# STM32_EVK_2.net
KiCad netlist of a schematic drawn in Altium Designer
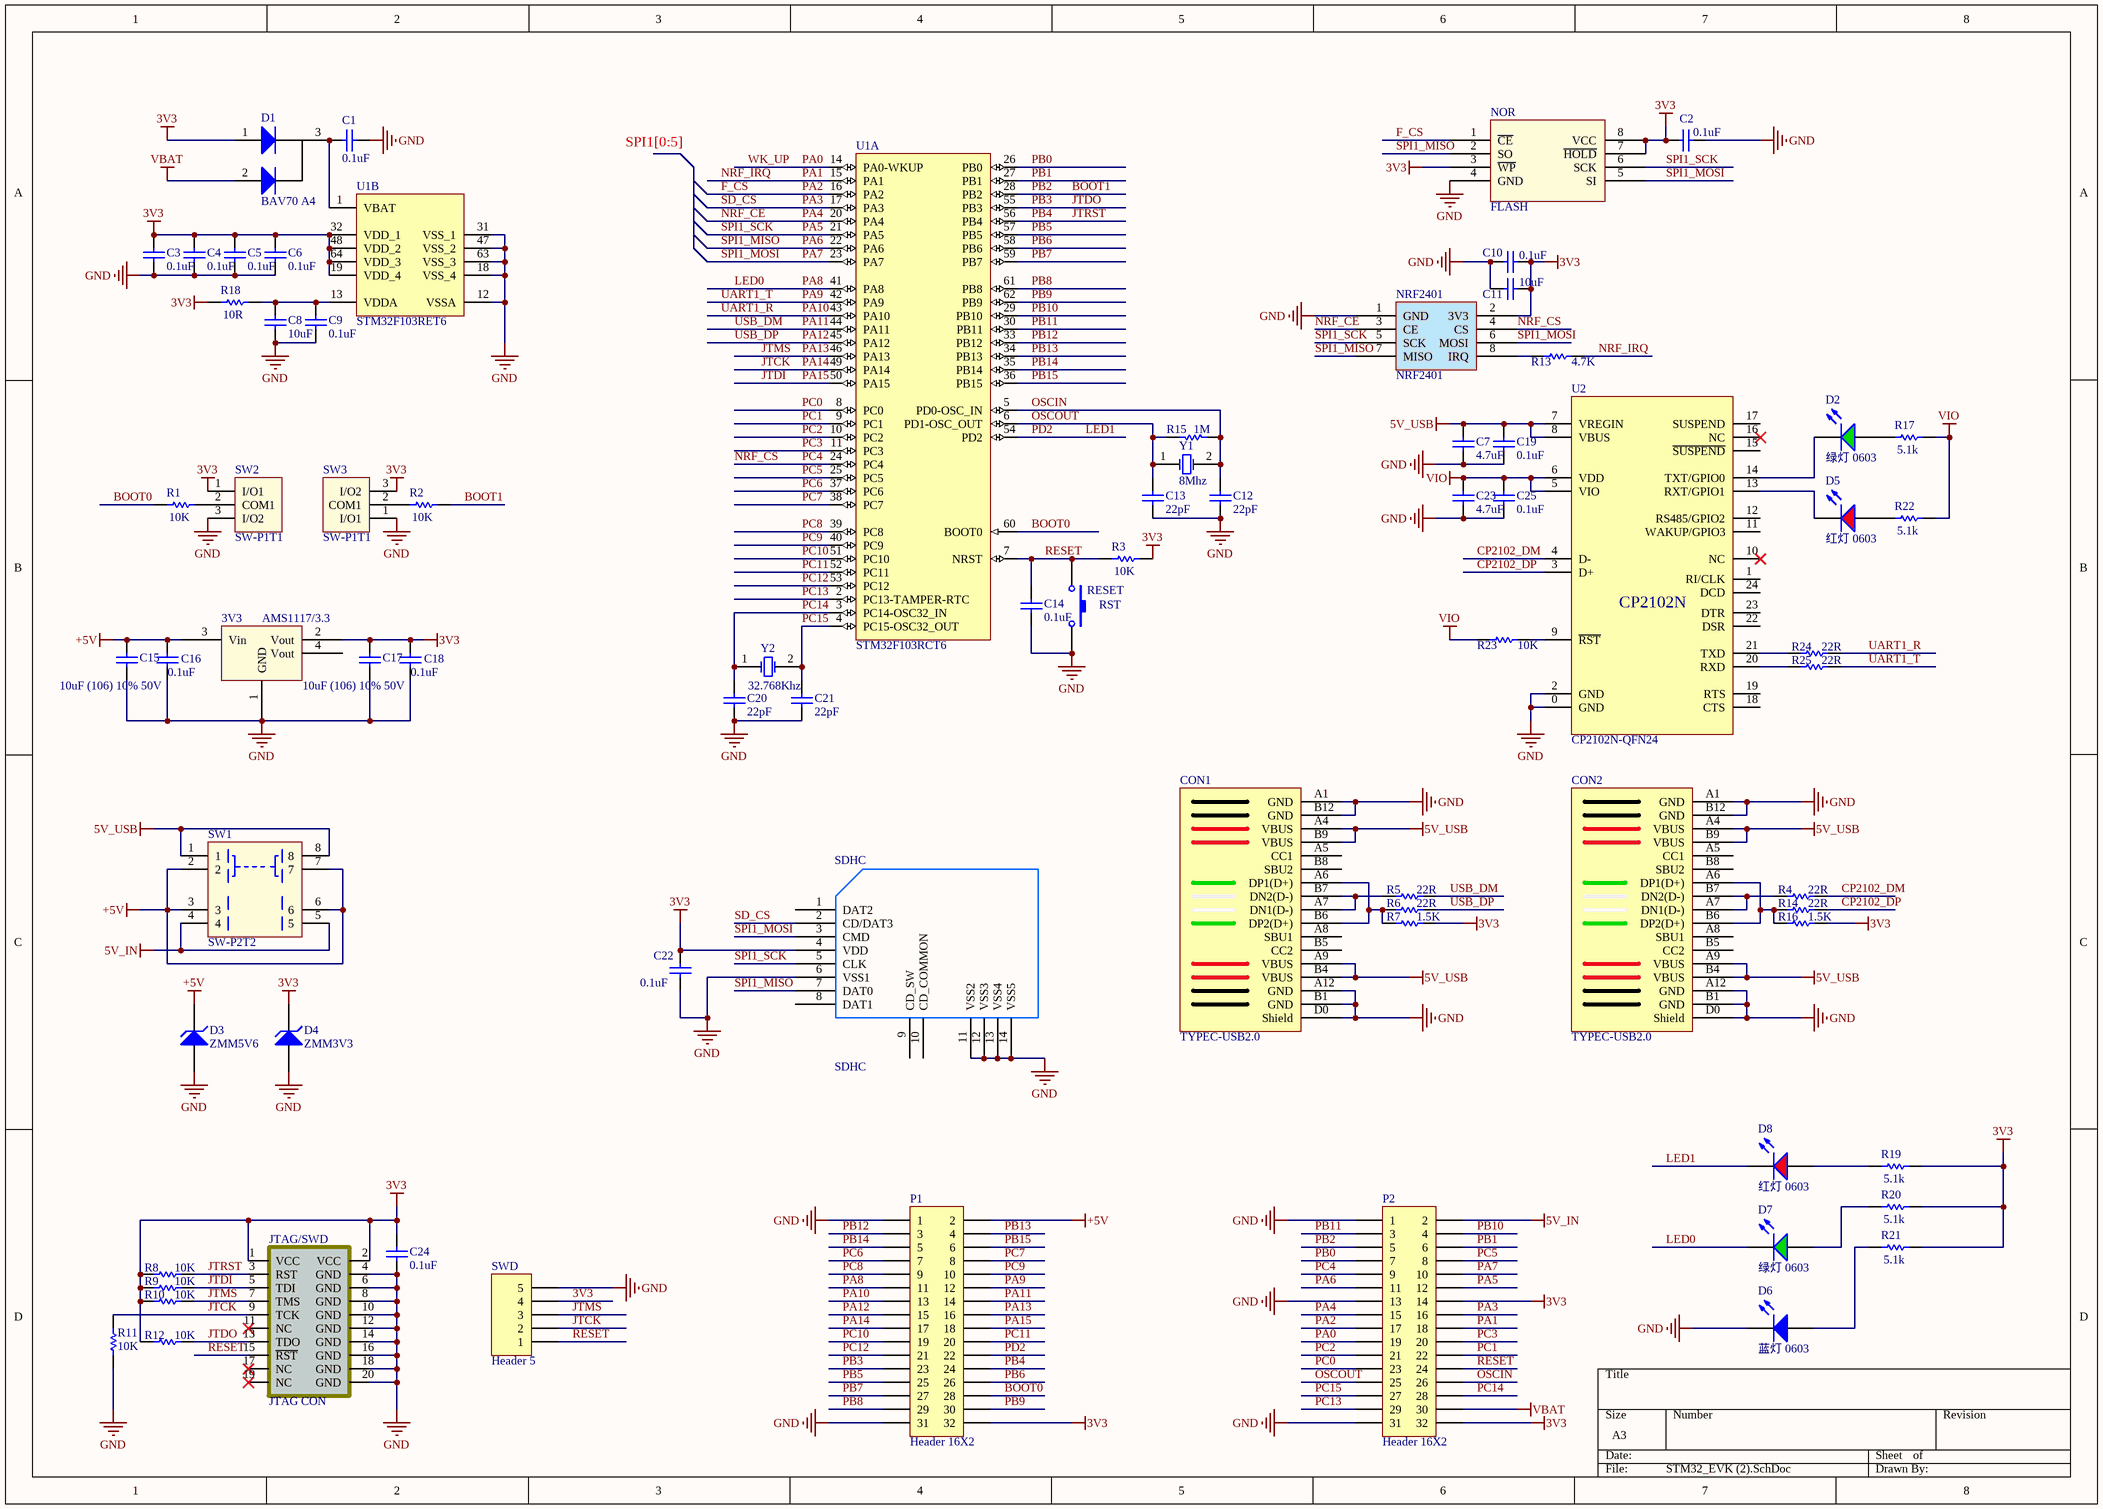
[diagram p0: STM32_EVK (2).SchDoc]

(export (version "E")
  (design (tool "Eeschema 10.0.6"))
  (components
    (comp (ref "3V3") (value "AMS1117/3.3") (footprint "LC-SOT-223") (libsource (lib "YJ1") (part "AMS1117")))
    (comp (ref "C1")
      (value "0.1uF")
      (footprint "LC-0603_C")
      (description "Capacitor")
      (fields (field (name "Comment") "Cap") (field (name "PUBLISHER") "Altium Limited"))
      (libsource (lib "Miscellaneous Devices") (part "Cap"))
    )
    (comp (ref "C2")
      (value "0.1uF")
      (footprint "LC-0603_C")
      (description "Capacitor")
      (fields (field (name "Comment") "Cap") (field (name "PUBLISHER") "Altium Limited"))
      (libsource (lib "Miscellaneous Devices") (part "Cap"))
    )
    (comp (ref "C3")
      (value "0.1uF")
      (footprint "LC-0603_C")
      (description "Capacitor")
      (fields (field (name "Comment") "Cap") (field (name "PUBLISHER") "Altium Limited"))
      (libsource (lib "Miscellaneous Devices") (part "Cap"))
    )
    (comp (ref "C4")
      (value "0.1uF")
      (footprint "LC-0603_C")
      (description "Capacitor")
      (fields (field (name "Comment") "Cap") (field (name "PUBLISHER") "Altium Limited"))
      (libsource (lib "Miscellaneous Devices") (part "Cap"))
    )
    (comp (ref "C5")
      (value "0.1uF")
      (footprint "LC-0603_C")
      (description "Capacitor")
      (fields (field (name "Comment") "Cap") (field (name "PUBLISHER") "Altium Limited"))
      (libsource (lib "Miscellaneous Devices") (part "Cap"))
    )
    (comp (ref "C6")
      (value "0.1uF")
      (footprint "LC-0603_C")
      (description "Capacitor")
      (fields (field (name "Comment") "Cap") (field (name "PUBLISHER") "Altium Limited"))
      (libsource (lib "Miscellaneous Devices") (part "Cap"))
    )
    (comp (ref "C7")
      (value "4.7uF")
      (footprint "LC-0603_C")
      (description "Capacitor")
      (fields (field (name "Comment") "Cap") (field (name "PUBLISHER") "Altium Limited"))
      (libsource (lib "Miscellaneous Devices") (part "Cap"))
    )
    (comp (ref "C8")
      (value "10uF")
      (footprint "LC-0603_C")
      (description "Capacitor")
      (fields (field (name "Comment") "Cap") (field (name "PUBLISHER") "Altium Limited"))
      (libsource (lib "Miscellaneous Devices") (part "Cap"))
    )
    (comp (ref "C9")
      (value "0.1uF")
      (footprint "LC-0603_C")
      (description "Capacitor")
      (fields (field (name "Comment") "Cap") (field (name "PUBLISHER") "Altium Limited"))
      (libsource (lib "Miscellaneous Devices") (part "Cap"))
    )
    (comp (ref "C10")
      (value "0.1uF")
      (footprint "LC-0603_C")
      (description "Capacitor")
      (fields (field (name "Comment") "Cap") (field (name "PUBLISHER") "Altium Limited"))
      (libsource (lib "Miscellaneous Devices") (part "Cap"))
    )
    (comp (ref "C11")
      (value "10uF")
      (footprint "LC-0603_C")
      (description "Capacitor")
      (fields (field (name "Comment") "Cap") (field (name "PUBLISHER") "Altium Limited"))
      (libsource (lib "Miscellaneous Devices") (part "Cap"))
    )
    (comp (ref "C12")
      (value "22pF")
      (footprint "LC-0603_C")
      (description "Capacitor")
      (fields (field (name "Comment") "Cap") (field (name "PUBLISHER") "Altium Limited"))
      (libsource (lib "Miscellaneous Devices") (part "Cap"))
    )
    (comp (ref "C13")
      (value "22pF")
      (footprint "LC-0603_C")
      (description "Capacitor")
      (fields (field (name "Comment") "Cap") (field (name "PUBLISHER") "Altium Limited"))
      (libsource (lib "Miscellaneous Devices") (part "Cap"))
    )
    (comp (ref "C14")
      (value "0.1uF")
      (footprint "LC-0603_C")
      (description "Capacitor")
      (fields (field (name "Comment") "Cap") (field (name "PUBLISHER") "Altium Limited"))
      (libsource (lib "Miscellaneous Devices") (part "Cap"))
    )
    (comp (ref "C15")
      (value "10uF (106) 10% 50V")
      (footprint "LC-1206_C")
      (description "贴片电容")
      (libsource (lib "Miscellaneous Devices LC") (part "1206 10uF (106) 10% 50V"))
    )
    (comp (ref "C16")
      (value "0.1uF")
      (footprint "LC-0603_C")
      (description "Capacitor (Semiconductor SIM Model)")
      (fields (field (name "Comment") "Cap Semi") (field (name "PUBLISHER") "Altium Limited"))
      (libsource (lib "Miscellaneous Devices") (part "Cap Semi"))
    )
    (comp (ref "C17")
      (value "10uF (106) 10% 50V")
      (footprint "LC-1206_C")
      (description "贴片电容")
      (libsource (lib "Miscellaneous Devices LC") (part "1206 10uF (106) 10% 50V"))
    )
    (comp (ref "C18")
      (value "0.1uF")
      (footprint "LC-0603_C")
      (description "Capacitor (Semiconductor SIM Model)")
      (fields (field (name "Comment") "Cap Semi") (field (name "PUBLISHER") "Altium Limited"))
      (libsource (lib "Miscellaneous Devices") (part "Cap Semi"))
    )
    (comp (ref "C19")
      (value "0.1uF")
      (footprint "LC-0603_C")
      (description "Capacitor")
      (fields (field (name "Comment") "Cap") (field (name "PUBLISHER") "Altium Limited"))
      (libsource (lib "Miscellaneous Devices") (part "Cap"))
    )
    (comp (ref "C20")
      (value "22pF")
      (footprint "LC-0603_C")
      (description "Capacitor")
      (fields (field (name "Comment") "Cap") (field (name "PUBLISHER") "Altium Limited"))
      (libsource (lib "Miscellaneous Devices") (part "Cap"))
    )
    (comp (ref "C21")
      (value "22pF")
      (footprint "LC-0603_C")
      (description "Capacitor")
      (fields (field (name "Comment") "Cap") (field (name "PUBLISHER") "Altium Limited"))
      (libsource (lib "Miscellaneous Devices") (part "Cap"))
    )
    (comp (ref "C22")
      (value "0.1uF")
      (footprint "LC-0603_C")
      (description "Capacitor")
      (fields (field (name "Comment") "Cap") (field (name "PUBLISHER") "Altium Limited"))
      (libsource (lib "Miscellaneous Devices") (part "Cap"))
    )
    (comp (ref "C23")
      (value "4.7uF")
      (footprint "LC-0603_C")
      (description "Capacitor")
      (fields (field (name "Comment") "Cap") (field (name "PUBLISHER") "Altium Limited"))
      (libsource (lib "Miscellaneous Devices") (part "Cap"))
    )
    (comp (ref "C24")
      (value "0.1uF")
      (footprint "LC-0603_C")
      (description "Capacitor")
      (fields (field (name "Comment") "Cap") (field (name "PUBLISHER") "Altium Limited"))
      (libsource (lib "Miscellaneous Devices") (part "Cap"))
    )
    (comp (ref "C25")
      (value "0.1uF")
      (footprint "LC-0603_C")
      (description "Capacitor")
      (fields (field (name "Comment") "Cap") (field (name "PUBLISHER") "Altium Limited"))
      (libsource (lib "Miscellaneous Devices") (part "Cap"))
    )
    (comp (ref "CON1")
      (value "TYPEC-USB2.0")
      (footprint "TYPEC-USB2.0")
      (libsource (lib "YJ1") (part "TYPEC-USB2.0"))
    )
    (comp (ref "CON2")
      (value "TYPEC-USB2.0")
      (footprint "TYPEC-USB2.0")
      (libsource (lib "YJ1") (part "TYPEC-USB2.0"))
    )
    (comp (ref "D1")
      (value "BAV70 A4")
      (footprint "LC-SOT-23(SOT-23-3)")
      (description "开关二极管")
      (libsource (lib "Miscellaneous Devices LC") (part "SOT-23 BAV70 A4"))
    )
    (comp (ref "D2")
      (value "绿灯 0603")
      (footprint "LC-0603_LED_S1")
      (description "发光二极管")
      (libsource (lib "Miscellaneous Devices LC") (part "0603 绿灯"))
    )
    (comp (ref "D3")
      (value "ZMM5V6")
      (footprint "LC-LL-34")
      (description "稳压二极管")
      (libsource (lib "Miscellaneous Devices LC") (part "LL-34 ZMM5V6"))
    )
    (comp (ref "D4")
      (value "ZMM3V3")
      (footprint "LC-LL-34")
      (description "稳压二极管")
      (libsource (lib "Miscellaneous Devices LC") (part "LL-34 ZMM3V3"))
    )
    (comp (ref "D5")
      (value "红灯 0603")
      (footprint "LC-0603_LED_S1")
      (description "发光二极管")
      (libsource (lib "Miscellaneous Devices LC") (part "0603 红灯"))
    )
    (comp (ref "D6")
      (value "蓝灯 0603")
      (footprint "LC-0603_LED_S1")
      (description "发光二极管")
      (libsource (lib "Miscellaneous Devices LC") (part "0603 蓝灯"))
    )
    (comp (ref "D7")
      (value "绿灯 0603")
      (footprint "LC-0603_LED_S1")
      (description "发光二极管")
      (libsource (lib "Miscellaneous Devices LC") (part "0603 绿灯"))
    )
    (comp (ref "D8")
      (value "红灯 0603")
      (footprint "LC-0603_LED_S1")
      (description "发光二极管")
      (libsource (lib "Miscellaneous Devices LC") (part "0603 红灯"))
    )
    (comp (ref "JTAG/SWD") (value "JTAG CON") (footprint "20Pin简牛") (libsource (lib "STM32F4") (part "JTAG")))
    (comp (ref "NOR") (value "FLASH") (footprint "M25P32_SOP8W") (libsource (lib "YJ1") (part "FLASH")))
    (comp (ref "NRF2401") (value "NRF2401") (footprint "HDR2X4") (libsource (lib "YJ1") (part "NRF2401")))
    (comp (ref "P1")
      (value "Header 16X2")
      (footprint "HDR2X16")
      (description "Header, 16-Pin, Dual row")
      (fields (field (name "PUBLISHER") "Altium Limited"))
      (libsource (lib "Miscellaneous Connectors") (part "Header 16X2"))
    )
    (comp (ref "P2")
      (value "Header 16X2")
      (footprint "HDR2X16")
      (description "Header, 16-Pin, Dual row")
      (fields (field (name "PUBLISHER") "Altium Limited"))
      (libsource (lib "Miscellaneous Connectors") (part "Header 16X2"))
    )
    (comp (ref "R1")
      (value "10K")
      (footprint "LC-0603_R")
      (description "Semiconductor Resistor")
      (fields (field (name "Comment") "Res Semi") (field (name "PUBLISHER") "Altium Limited"))
      (libsource (lib "Miscellaneous Devices") (part "Res Semi"))
    )
    (comp (ref "R2")
      (value "10K")
      (footprint "LC-0603_R")
      (description "Semiconductor Resistor")
      (fields (field (name "Comment") "Res Semi") (field (name "PUBLISHER") "Altium Limited"))
      (libsource (lib "Miscellaneous Devices") (part "Res Semi"))
    )
    (comp (ref "R3")
      (value "10K")
      (footprint "LC-0603_R")
      (description "Semiconductor Resistor")
      (fields (field (name "Comment") "Res Semi") (field (name "PUBLISHER") "Altium Limited"))
      (libsource (lib "Miscellaneous Devices") (part "Res Semi"))
    )
    (comp (ref "R4")
      (value "22R")
      (footprint "LC-0603_R")
      (description "Semiconductor Resistor")
      (fields (field (name "Comment") "Res Semi") (field (name "PUBLISHER") "Altium Limited"))
      (libsource (lib "Miscellaneous Devices") (part "Res Semi"))
    )
    (comp (ref "R5")
      (value "22R")
      (footprint "LC-0603_R")
      (description "Semiconductor Resistor")
      (fields (field (name "Comment") "Res Semi") (field (name "PUBLISHER") "Altium Limited"))
      (libsource (lib "Miscellaneous Devices") (part "Res Semi"))
    )
    (comp (ref "R6")
      (value "22R")
      (footprint "LC-0603_R")
      (description "Semiconductor Resistor")
      (fields (field (name "Comment") "Res Semi") (field (name "PUBLISHER") "Altium Limited"))
      (libsource (lib "Miscellaneous Devices") (part "Res Semi"))
    )
    (comp (ref "R7")
      (value "1.5K")
      (footprint "LC-0603_R")
      (description "Semiconductor Resistor")
      (fields (field (name "Comment") "Res Semi") (field (name "PUBLISHER") "Altium Limited"))
      (libsource (lib "Miscellaneous Devices") (part "Res Semi"))
    )
    (comp (ref "R8")
      (value "10K")
      (footprint "LC-0603_R")
      (description "Semiconductor Resistor")
      (fields (field (name "Comment") "Res Semi") (field (name "PUBLISHER") "Altium Limited"))
      (libsource (lib "Miscellaneous Devices") (part "Res Semi"))
    )
    (comp (ref "R9")
      (value "10K")
      (footprint "LC-0603_R")
      (description "Semiconductor Resistor")
      (fields (field (name "Comment") "Res Semi") (field (name "PUBLISHER") "Altium Limited"))
      (libsource (lib "Miscellaneous Devices") (part "Res Semi"))
    )
    (comp (ref "R10")
      (value "10K")
      (footprint "LC-0603_R")
      (description "Semiconductor Resistor")
      (fields (field (name "Comment") "Res Semi") (field (name "PUBLISHER") "Altium Limited"))
      (libsource (lib "Miscellaneous Devices") (part "Res Semi"))
    )
    (comp (ref "R11")
      (value "10K")
      (footprint "LC-0603_R")
      (description "Semiconductor Resistor")
      (fields (field (name "Comment") "Res Semi") (field (name "PUBLISHER") "Altium Limited"))
      (libsource (lib "Miscellaneous Devices") (part "Res Semi"))
    )
    (comp (ref "R12")
      (value "10K")
      (footprint "LC-0603_R")
      (description "Semiconductor Resistor")
      (fields (field (name "Comment") "Res Semi") (field (name "PUBLISHER") "Altium Limited"))
      (libsource (lib "Miscellaneous Devices") (part "Res Semi"))
    )
    (comp (ref "R13")
      (value "4.7K")
      (footprint "LC-0603_R")
      (description "Semiconductor Resistor")
      (fields (field (name "Comment") "Res Semi") (field (name "PUBLISHER") "Altium Limited"))
      (libsource (lib "Miscellaneous Devices") (part "Res Semi"))
    )
    (comp (ref "R14")
      (value "22R")
      (footprint "LC-0603_R")
      (description "Semiconductor Resistor")
      (fields (field (name "Comment") "Res Semi") (field (name "PUBLISHER") "Altium Limited"))
      (libsource (lib "Miscellaneous Devices") (part "Res Semi"))
    )
    (comp (ref "R15")
      (value "1M")
      (footprint "LC-0603_R")
      (description "Semiconductor Resistor")
      (fields (field (name "Comment") "Res Semi") (field (name "PUBLISHER") "Altium Limited"))
      (libsource (lib "Miscellaneous Devices") (part "Res Semi"))
    )
    (comp (ref "R16")
      (value "1.5K")
      (footprint "LC-0603_R")
      (description "Semiconductor Resistor")
      (fields (field (name "Comment") "Res Semi") (field (name "PUBLISHER") "Altium Limited"))
      (libsource (lib "Miscellaneous Devices") (part "Res Semi"))
    )
    (comp (ref "R17")
      (value "5.1k")
      (footprint "LC-0603_R")
      (description "Semiconductor Resistor")
      (fields (field (name "Comment") "Res Semi") (field (name "PUBLISHER") "Altium Limited"))
      (libsource (lib "Miscellaneous Devices") (part "Res Semi"))
    )
    (comp (ref "R18")
      (value "10R")
      (footprint "LC-0603_R")
      (description "Semiconductor Resistor")
      (fields (field (name "Comment") "Res Semi") (field (name "PUBLISHER") "Altium Limited"))
      (libsource (lib "Miscellaneous Devices") (part "Res Semi"))
    )
    (comp (ref "R19")
      (value "5.1k")
      (footprint "LC-0603_R")
      (description "Semiconductor Resistor")
      (fields (field (name "Comment") "Res Semi") (field (name "PUBLISHER") "Altium Limited"))
      (libsource (lib "Miscellaneous Devices") (part "Res Semi"))
    )
    (comp (ref "R20")
      (value "5.1k")
      (footprint "LC-0603_R")
      (description "Semiconductor Resistor")
      (fields (field (name "Comment") "Res Semi") (field (name "PUBLISHER") "Altium Limited"))
      (libsource (lib "Miscellaneous Devices") (part "Res Semi"))
    )
    (comp (ref "R21")
      (value "5.1k")
      (footprint "LC-0603_R")
      (description "Semiconductor Resistor")
      (fields (field (name "Comment") "Res Semi") (field (name "PUBLISHER") "Altium Limited"))
      (libsource (lib "Miscellaneous Devices") (part "Res Semi"))
    )
    (comp (ref "R22")
      (value "5.1k")
      (footprint "LC-0603_R")
      (description "Semiconductor Resistor")
      (fields (field (name "Comment") "Res Semi") (field (name "PUBLISHER") "Altium Limited"))
      (libsource (lib "Miscellaneous Devices") (part "Res Semi"))
    )
    (comp (ref "R23")
      (value "10K")
      (footprint "LC-0603_R")
      (description "Semiconductor Resistor")
      (fields (field (name "Comment") "Res Semi") (field (name "PUBLISHER") "Altium Limited"))
      (libsource (lib "Miscellaneous Devices") (part "Res Semi"))
    )
    (comp (ref "R24")
      (value "22R")
      (footprint "LC-0603_R")
      (description "Semiconductor Resistor")
      (fields (field (name "Comment") "Res Semi") (field (name "PUBLISHER") "Altium Limited"))
      (libsource (lib "Miscellaneous Devices") (part "Res Semi"))
    )
    (comp (ref "R25")
      (value "22R")
      (footprint "LC-0603_R")
      (description "Semiconductor Resistor")
      (fields (field (name "Comment") "Res Semi") (field (name "PUBLISHER") "Altium Limited"))
      (libsource (lib "Miscellaneous Devices") (part "Res Semi"))
    )
    (comp (ref "RESET")
      (value "RST")
      (footprint "ALPS_SKPMA_KEY")
      (description "Switch")
      (fields (field (name "PUBLISHER") "Altium Limited"))
      (libsource (lib "Miscellaneous Devices") (part "SW-PB"))
    )
    (comp (ref "SDHC") (value "SDHC") (footprint "microSD") (libsource (lib "YJ1") (part "SDHC")))
    (comp (ref "SW1") (value "SW-P2T2") (footprint "SW-P2T2") (libsource (lib "YJ1") (part "SW-P2T2")))
    (comp (ref "SW2") (value "SW-P1T1") (footprint "SW-P1T1") (libsource (lib "YJ1") (part "SW-P1T1")))
    (comp (ref "SW3") (value "SW-P1T1") (footprint "SW-P1T1-JUMP") (libsource (lib "") (part "SW-P1T1_1")))
    (comp (ref "SWD")
      (value "Header 5")
      (footprint "HDR1X5")
      (description "Header, 5-Pin")
      (fields (field (name "PUBLISHER") "Altium Limited"))
      (libsource (lib "Miscellaneous Connectors") (part "Header 5"))
    )
    (comp (ref "U1")
      (value "STM32F103RCT6")
      (footprint "LC-LQFP-64_10x10x05P")
      (fields (field (name "PARTNUMBER") "STM32F103RET6"))
      (libsource (lib "STMicroelectronics STM32 F1") (part "STM32F103RET6"))
    )
    (comp (ref "U2")
      (value "CP2102N-QFN24")
      (footprint "LC-QFN-24_4x4x05P")
      (libsource (lib "YJ1") (part "CP2102N-QFN24"))
    )
    (comp (ref "Y1")
      (value "8Mhz")
      (footprint "XTAL-RAD-0.2")
      (description "Crystal Oscillator")
      (fields (field (name "PUBLISHER") "Altium Limited"))
      (libsource (lib "Miscellaneous Devices") (part "XTAL"))
    )
    (comp (ref "Y2")
      (value "32.768Khz")
      (footprint "32768_3*8_圆筒晶振")
      (description "Crystal Oscillator")
      (fields (field (name "PUBLISHER") "Altium Limited"))
      (libsource (lib "Miscellaneous Devices") (part "XTAL"))
    )
  )
  (nets
    (net (code "1") (name "+5V") (class "Default")
      (node (ref "3V3") (pin "3") (pinfunction "Vin_3") (pintype "passive"))
      (node (ref "C15") (pin "2") (pinfunction "2_2") (pintype "passive"))
      (node (ref "C16") (pin "2") (pinfunction "2_2") (pintype "passive"))
      (node (ref "D3") (pin "2") (pinfunction "K_2") (pintype "passive"))
      (node (ref "P1") (pin "2") (pinfunction "2_2") (pintype "passive"))
      (node (ref "SW1") (pin "2") (pinfunction "2_2") (pintype "passive"))
      (node (ref "SW1") (pin "3") (pinfunction "3_3") (pintype "passive"))
      (node (ref "SW1") (pin "6") (pinfunction "6_6") (pintype "passive"))
      (node (ref "SW1") (pin "7") (pinfunction "7_7") (pintype "passive"))
    )
    (net (code "2") (name "/BOOT0") (class "Default")
      (node (ref "P1") (pin "28") (pinfunction "28_28") (pintype "passive"))
      (node (ref "R1") (pin "1") (pinfunction "1_1") (pintype "passive"))
      (node (ref "U1") (pin "60") (pinfunction "BOOT0_60") (pintype "input"))
    )
    (net (code "3") (name "/BOOT1") (class "Default")
      (node (ref "P2") (pin "5") (pinfunction "5_5") (pintype "passive"))
      (node (ref "R2") (pin "2") (pinfunction "2_2") (pintype "passive"))
      (node (ref "U1") (pin "28") (pinfunction "PB2_28") (pintype "bidirectional"))
    )
    (net (code "4") (name "/CP2102_DM") (class "Default")
      (node (ref "R4") (pin "2") (pinfunction "2_2") (pintype "passive"))
      (node (ref "U2") (pin "4") (pinfunction "D-_4") (pintype "passive"))
    )
    (net (code "5") (name "/CP2102_DP") (class "Default")
      (node (ref "R14") (pin "2") (pinfunction "2_2") (pintype "passive"))
      (node (ref "U2") (pin "3") (pinfunction "D+_3") (pintype "passive"))
    )
    (net (code "6") (name "/F_CS") (class "Default")
      (node (ref "NOR") (pin "1") (pinfunction "~{CE}_1") (pintype "passive"))
      (node (ref "P2") (pin "17") (pinfunction "17_17") (pintype "passive"))
      (node (ref "U1") (pin "16") (pinfunction "PA2_16") (pintype "bidirectional"))
    )
    (net (code "7") (name "/JTCK") (class "Default")
      (node (ref "JTAG/SWD") (pin "9") (pinfunction "TCK_9") (pintype "passive"))
      (node (ref "P1") (pin "17") (pinfunction "17_17") (pintype "passive"))
      (node (ref "R11") (pin "2") (pinfunction "2_2") (pintype "passive"))
      (node (ref "SWD") (pin "2") (pinfunction "2_2") (pintype "passive"))
      (node (ref "U1") (pin "49") (pinfunction "PA14_49") (pintype "bidirectional"))
    )
    (net (code "8") (name "/JTDI") (class "Default")
      (node (ref "JTAG/SWD") (pin "5") (pinfunction "TDI_5") (pintype "passive"))
      (node (ref "P1") (pin "18") (pinfunction "18_18") (pintype "passive"))
      (node (ref "R9") (pin "2") (pinfunction "2_2") (pintype "passive"))
      (node (ref "U1") (pin "50") (pinfunction "PA15_50") (pintype "bidirectional"))
    )
    (net (code "9") (name "/JTDO") (class "Default")
      (node (ref "JTAG/SWD") (pin "13") (pinfunction "TDO_13") (pintype "passive"))
      (node (ref "P1") (pin "23") (pinfunction "23_23") (pintype "passive"))
      (node (ref "R12") (pin "2") (pinfunction "2_2") (pintype "passive"))
      (node (ref "U1") (pin "55") (pinfunction "PB3_55") (pintype "bidirectional"))
    )
    (net (code "10") (name "/JTMS") (class "Default")
      (node (ref "JTAG/SWD") (pin "7") (pinfunction "TMS_7") (pintype "passive"))
      (node (ref "P1") (pin "16") (pinfunction "16_16") (pintype "passive"))
      (node (ref "R10") (pin "2") (pinfunction "2_2") (pintype "passive"))
      (node (ref "SWD") (pin "3") (pinfunction "3_3") (pintype "passive"))
      (node (ref "U1") (pin "46") (pinfunction "PA13_46") (pintype "bidirectional"))
    )
    (net (code "11") (name "/JTRST") (class "Default")
      (node (ref "JTAG/SWD") (pin "3") (pinfunction "RST_3") (pintype "passive"))
      (node (ref "P1") (pin "24") (pinfunction "24_24") (pintype "passive"))
      (node (ref "R8") (pin "2") (pinfunction "2_2") (pintype "passive"))
      (node (ref "U1") (pin "56") (pinfunction "PB4_56") (pintype "bidirectional"))
    )
    (net (code "12") (name "/LED0") (class "Default")
      (node (ref "D7") (pin "K") (pinfunction "K_K") (pintype "passive"))
      (node (ref "P1") (pin "11") (pinfunction "11_11") (pintype "passive"))
      (node (ref "U1") (pin "41") (pinfunction "PA8_41") (pintype "bidirectional"))
    )
    (net (code "13") (name "/LED1") (class "Default")
      (node (ref "D8") (pin "K") (pinfunction "K_K") (pintype "passive"))
      (node (ref "P1") (pin "22") (pinfunction "22_22") (pintype "passive"))
      (node (ref "U1") (pin "54") (pinfunction "PD2_54") (pintype "bidirectional"))
    )
    (net (code "14") (name "/NRF_CE") (class "Default")
      (node (ref "NRF2401") (pin "3") (pinfunction "CE_3") (pintype "passive"))
      (node (ref "P2") (pin "15") (pinfunction "15_15") (pintype "passive"))
      (node (ref "U1") (pin "20") (pinfunction "PA4_20") (pintype "bidirectional"))
    )
    (net (code "15") (name "/NRF_CS") (class "Default")
      (node (ref "NRF2401") (pin "4") (pinfunction "CS_4") (pintype "passive"))
      (node (ref "P2") (pin "9") (pinfunction "9_9") (pintype "passive"))
      (node (ref "U1") (pin "24") (pinfunction "PC4_24") (pintype "bidirectional"))
    )
    (net (code "16") (name "/NRF_IRQ") (class "Default")
      (node (ref "P2") (pin "18") (pinfunction "18_18") (pintype "passive"))
      (node (ref "R13") (pin "2") (pinfunction "2_2") (pintype "passive"))
      (node (ref "U1") (pin "15") (pinfunction "PA1_15") (pintype "bidirectional"))
    )
    (net (code "17") (name "/OSCIN") (class "Default")
      (node (ref "C12") (pin "2") (pinfunction "2_2") (pintype "passive"))
      (node (ref "P2") (pin "26") (pinfunction "26_26") (pintype "passive"))
      (node (ref "R15") (pin "1") (pinfunction "1_1") (pintype "passive"))
      (node (ref "U1") (pin "5") (pinfunction "PD0-OSC_IN_5") (pintype "bidirectional"))
      (node (ref "Y1") (pin "2") (pinfunction "OSC2_2") (pintype "passive"))
    )
    (net (code "18") (name "/OSCOUT") (class "Default")
      (node (ref "C13") (pin "2") (pinfunction "2_2") (pintype "passive"))
      (node (ref "P2") (pin "25") (pinfunction "25_25") (pintype "passive"))
      (node (ref "R15") (pin "2") (pinfunction "2_2") (pintype "passive"))
      (node (ref "U1") (pin "6") (pinfunction "PD1-OSC_OUT_6") (pintype "bidirectional"))
      (node (ref "Y1") (pin "1") (pinfunction "OSC1_1") (pintype "passive"))
    )
    (net (code "19") (name "/PA0") (class "Default")
      (node (ref "P2") (pin "19") (pinfunction "19_19") (pintype "passive"))
      (node (ref "U1") (pin "14") (pinfunction "PA0-WKUP_14") (pintype "bidirectional"))
    )
    (net (code "20") (name "/PA3") (class "Default")
      (node (ref "P2") (pin "16") (pinfunction "16_16") (pintype "passive"))
      (node (ref "SDHC") (pin "2") (pinfunction "CD/DAT3_2") (pintype "passive"))
      (node (ref "U1") (pin "17") (pinfunction "PA3_17") (pintype "bidirectional"))
    )
    (net (code "21") (name "/PA5") (class "Default")
      (node (ref "NOR") (pin "6") (pinfunction "SCK_6") (pintype "passive"))
      (node (ref "NRF2401") (pin "5") (pinfunction "SCK_5") (pintype "passive"))
      (node (ref "P2") (pin "12") (pinfunction "12_12") (pintype "passive"))
      (node (ref "SDHC") (pin "5") (pinfunction "CLK_5") (pintype "passive"))
      (node (ref "U1") (pin "21") (pinfunction "PA5_21") (pintype "bidirectional"))
    )
    (net (code "22") (name "/PA6") (class "Default")
      (node (ref "NOR") (pin "2") (pinfunction "SO_2") (pintype "passive"))
      (node (ref "NRF2401") (pin "7") (pinfunction "MISO_7") (pintype "passive"))
      (node (ref "P2") (pin "11") (pinfunction "11_11") (pintype "passive"))
      (node (ref "SDHC") (pin "7") (pinfunction "DAT0_7") (pintype "passive"))
      (node (ref "U1") (pin "22") (pinfunction "PA6_22") (pintype "bidirectional"))
    )
    (net (code "23") (name "/PA7") (class "Default")
      (node (ref "NOR") (pin "5") (pinfunction "SI_5") (pintype "passive"))
      (node (ref "NRF2401") (pin "6") (pinfunction "MOSI_6") (pintype "passive"))
      (node (ref "P2") (pin "10") (pinfunction "10_10") (pintype "passive"))
      (node (ref "SDHC") (pin "3") (pinfunction "CMD_3") (pintype "passive"))
      (node (ref "U1") (pin "23") (pinfunction "PA7_23") (pintype "bidirectional"))
    )
    (net (code "24") (name "/PA9") (class "Default")
      (node (ref "P1") (pin "12") (pinfunction "12_12") (pintype "passive"))
      (node (ref "R25") (pin "2") (pinfunction "2_2") (pintype "passive"))
      (node (ref "U1") (pin "42") (pinfunction "PA9_42") (pintype "bidirectional"))
    )
    (net (code "25") (name "/PA10") (class "Default")
      (node (ref "P1") (pin "13") (pinfunction "13_13") (pintype "passive"))
      (node (ref "R24") (pin "2") (pinfunction "2_2") (pintype "passive"))
      (node (ref "U1") (pin "43") (pinfunction "PA10_43") (pintype "bidirectional"))
    )
    (net (code "26") (name "/PA11") (class "Default")
      (node (ref "P1") (pin "14") (pinfunction "14_14") (pintype "passive"))
      (node (ref "R5") (pin "2") (pinfunction "2_2") (pintype "passive"))
      (node (ref "U1") (pin "44") (pinfunction "PA11_44") (pintype "bidirectional"))
    )
    (net (code "27") (name "/PA12") (class "Default")
      (node (ref "P1") (pin "15") (pinfunction "15_15") (pintype "passive"))
      (node (ref "R6") (pin "2") (pinfunction "2_2") (pintype "passive"))
      (node (ref "U1") (pin "45") (pinfunction "PA12_45") (pintype "bidirectional"))
    )
    (net (code "28") (name "/PB0") (class "Default")
      (node (ref "P2") (pin "7") (pinfunction "7_7") (pintype "passive"))
      (node (ref "U1") (pin "26") (pinfunction "PB0_26") (pintype "bidirectional"))
    )
    (net (code "29") (name "/PB1") (class "Default")
      (node (ref "P2") (pin "6") (pinfunction "6_6") (pintype "passive"))
      (node (ref "U1") (pin "27") (pinfunction "PB1_27") (pintype "bidirectional"))
    )
    (net (code "30") (name "/PB5") (class "Default")
      (node (ref "P1") (pin "25") (pinfunction "25_25") (pintype "passive"))
      (node (ref "U1") (pin "57") (pinfunction "PB5_57") (pintype "bidirectional"))
    )
    (net (code "31") (name "/PB6") (class "Default")
      (node (ref "P1") (pin "26") (pinfunction "26_26") (pintype "passive"))
      (node (ref "U1") (pin "58") (pinfunction "PB6_58") (pintype "bidirectional"))
    )
    (net (code "32") (name "/PB7") (class "Default")
      (node (ref "P1") (pin "27") (pinfunction "27_27") (pintype "passive"))
      (node (ref "U1") (pin "59") (pinfunction "PB7_59") (pintype "bidirectional"))
    )
    (net (code "33") (name "/PB8") (class "Default")
      (node (ref "P1") (pin "29") (pinfunction "29_29") (pintype "passive"))
      (node (ref "U1") (pin "61") (pinfunction "PB8_61") (pintype "bidirectional"))
    )
    (net (code "34") (name "/PB9") (class "Default")
      (node (ref "P1") (pin "30") (pinfunction "30_30") (pintype "passive"))
      (node (ref "U1") (pin "62") (pinfunction "PB9_62") (pintype "bidirectional"))
    )
    (net (code "35") (name "/PB10") (class "Default")
      (node (ref "P2") (pin "4") (pinfunction "4_4") (pintype "passive"))
      (node (ref "U1") (pin "29") (pinfunction "PB10_29") (pintype "bidirectional"))
    )
    (net (code "36") (name "/PB11") (class "Default")
      (node (ref "P2") (pin "3") (pinfunction "3_3") (pintype "passive"))
      (node (ref "U1") (pin "30") (pinfunction "PB11_30") (pintype "bidirectional"))
    )
    (net (code "37") (name "/PB12") (class "Default")
      (node (ref "P1") (pin "3") (pinfunction "3_3") (pintype "passive"))
      (node (ref "U1") (pin "33") (pinfunction "PB12_33") (pintype "bidirectional"))
    )
    (net (code "38") (name "/PB13") (class "Default")
      (node (ref "P1") (pin "4") (pinfunction "4_4") (pintype "passive"))
      (node (ref "U1") (pin "34") (pinfunction "PB13_34") (pintype "bidirectional"))
    )
    (net (code "39") (name "/PB14") (class "Default")
      (node (ref "P1") (pin "5") (pinfunction "5_5") (pintype "passive"))
      (node (ref "U1") (pin "35") (pinfunction "PB14_35") (pintype "bidirectional"))
    )
    (net (code "40") (name "/PB15") (class "Default")
      (node (ref "P1") (pin "6") (pinfunction "6_6") (pintype "passive"))
      (node (ref "U1") (pin "36") (pinfunction "PB15_36") (pintype "bidirectional"))
    )
    (net (code "41") (name "/PC0") (class "Default")
      (node (ref "P2") (pin "23") (pinfunction "23_23") (pintype "passive"))
      (node (ref "U1") (pin "8") (pinfunction "PC0_8") (pintype "bidirectional"))
    )
    (net (code "42") (name "/PC1") (class "Default")
      (node (ref "P2") (pin "22") (pinfunction "22_22") (pintype "passive"))
      (node (ref "U1") (pin "9") (pinfunction "PC1_9") (pintype "bidirectional"))
    )
    (net (code "43") (name "/PC2") (class "Default")
      (node (ref "P2") (pin "21") (pinfunction "21_21") (pintype "passive"))
      (node (ref "U1") (pin "10") (pinfunction "PC2_10") (pintype "bidirectional"))
    )
    (net (code "44") (name "/PC3") (class "Default")
      (node (ref "P2") (pin "20") (pinfunction "20_20") (pintype "passive"))
      (node (ref "U1") (pin "11") (pinfunction "PC3_11") (pintype "bidirectional"))
    )
    (net (code "45") (name "/PC5") (class "Default")
      (node (ref "P2") (pin "8") (pinfunction "8_8") (pintype "passive"))
      (node (ref "U1") (pin "25") (pinfunction "PC5_25") (pintype "bidirectional"))
    )
    (net (code "46") (name "/PC6") (class "Default")
      (node (ref "P1") (pin "7") (pinfunction "7_7") (pintype "passive"))
      (node (ref "U1") (pin "37") (pinfunction "PC6_37") (pintype "bidirectional"))
    )
    (net (code "47") (name "/PC7") (class "Default")
      (node (ref "P1") (pin "8") (pinfunction "8_8") (pintype "passive"))
      (node (ref "U1") (pin "38") (pinfunction "PC7_38") (pintype "bidirectional"))
    )
    (net (code "48") (name "/PC8") (class "Default")
      (node (ref "P1") (pin "9") (pinfunction "9_9") (pintype "passive"))
      (node (ref "U1") (pin "39") (pinfunction "PC8_39") (pintype "bidirectional"))
    )
    (net (code "49") (name "/PC9") (class "Default")
      (node (ref "P1") (pin "10") (pinfunction "10_10") (pintype "passive"))
      (node (ref "U1") (pin "40") (pinfunction "PC9_40") (pintype "bidirectional"))
    )
    (net (code "50") (name "/PC10") (class "Default")
      (node (ref "P1") (pin "19") (pinfunction "19_19") (pintype "passive"))
      (node (ref "U1") (pin "51") (pinfunction "PC10_51") (pintype "bidirectional"))
    )
    (net (code "51") (name "/PC11") (class "Default")
      (node (ref "P1") (pin "20") (pinfunction "20_20") (pintype "passive"))
      (node (ref "U1") (pin "52") (pinfunction "PC11_52") (pintype "bidirectional"))
    )
    (net (code "52") (name "/PC12") (class "Default")
      (node (ref "P1") (pin "21") (pinfunction "21_21") (pintype "passive"))
      (node (ref "U1") (pin "53") (pinfunction "PC12_53") (pintype "bidirectional"))
    )
    (net (code "53") (name "/PC13") (class "Default")
      (node (ref "P2") (pin "29") (pinfunction "29_29") (pintype "passive"))
      (node (ref "U1") (pin "2") (pinfunction "PC13-TAMPER-RTC_2") (pintype "bidirectional"))
    )
    (net (code "54") (name "/PC14") (class "Default")
      (node (ref "C20") (pin "2") (pinfunction "2_2") (pintype "passive"))
      (node (ref "P2") (pin "28") (pinfunction "28_28") (pintype "passive"))
      (node (ref "U1") (pin "3") (pinfunction "PC14-OSC32_IN_3") (pintype "bidirectional"))
      (node (ref "Y2") (pin "1") (pinfunction "OSC1_1") (pintype "passive"))
    )
    (net (code "55") (name "/PC15") (class "Default")
      (node (ref "C21") (pin "2") (pinfunction "2_2") (pintype "passive"))
      (node (ref "P2") (pin "27") (pinfunction "27_27") (pintype "passive"))
      (node (ref "U1") (pin "4") (pinfunction "PC15-OSC32_OUT_4") (pintype "bidirectional"))
      (node (ref "Y2") (pin "2") (pinfunction "OSC2_2") (pintype "passive"))
    )
    (net (code "56") (name "/RESET") (class "Default")
      (node (ref "C14") (pin "2") (pinfunction "2_2") (pintype "passive"))
      (node (ref "JTAG/SWD") (pin "15") (pinfunction "~{RST}_15") (pintype "passive"))
      (node (ref "P2") (pin "24") (pinfunction "24_24") (pintype "passive"))
      (node (ref "R3") (pin "1") (pinfunction "1_1") (pintype "passive"))
      (node (ref "RESET") (pin "1") (pinfunction "1_1") (pintype "passive"))
      (node (ref "SWD") (pin "1") (pinfunction "1_1") (pintype "passive"))
      (node (ref "U1") (pin "7") (pinfunction "NRST_7") (pintype "bidirectional"))
    )
    (net (code "57") (name "3V3") (class "Default")
      (node (ref "3V3") (pin "2") (pinfunction "Vout_2") (pintype "passive"))
      (node (ref "C10") (pin "1") (pinfunction "1_1") (pintype "passive"))
      (node (ref "C11") (pin "1") (pinfunction "1_1") (pintype "passive"))
      (node (ref "C17") (pin "2") (pinfunction "2_2") (pintype "passive"))
      (node (ref "C18") (pin "2") (pinfunction "2_2") (pintype "passive"))
      (node (ref "C2") (pin "2") (pinfunction "2_2") (pintype "passive"))
      (node (ref "C22") (pin "2") (pinfunction "2_2") (pintype "passive"))
      (node (ref "C24") (pin "2") (pinfunction "2_2") (pintype "passive"))
      (node (ref "C3") (pin "2") (pinfunction "2_2") (pintype "passive"))
      (node (ref "C4") (pin "2") (pinfunction "2_2") (pintype "passive"))
      (node (ref "C5") (pin "2") (pinfunction "2_2") (pintype "passive"))
      (node (ref "C6") (pin "2") (pinfunction "2_2") (pintype "passive"))
      (node (ref "D1") (pin "1") (pinfunction "A_1") (pintype "passive"))
      (node (ref "D4") (pin "2") (pinfunction "K_2") (pintype "passive"))
      (node (ref "JTAG/SWD") (pin "1") (pinfunction "VCC_1") (pintype "passive"))
      (node (ref "JTAG/SWD") (pin "2") (pinfunction "VCC_2") (pintype "passive"))
      (node (ref "NOR") (pin "3") (pinfunction "~{WP}_3") (pintype "passive"))
      (node (ref "NOR") (pin "7") (pinfunction "~{HOLD}_7") (pintype "passive"))
      (node (ref "NOR") (pin "8") (pinfunction "VCC_8") (pintype "passive"))
      (node (ref "NRF2401") (pin "2") (pinfunction "3V3_2") (pintype "passive"))
      (node (ref "P1") (pin "32") (pinfunction "32_32") (pintype "passive"))
      (node (ref "P2") (pin "14") (pinfunction "14_14") (pintype "passive"))
      (node (ref "P2") (pin "32") (pinfunction "32_32") (pintype "passive"))
      (node (ref "R10") (pin "1") (pinfunction "1_1") (pintype "passive"))
      (node (ref "R12") (pin "1") (pinfunction "1_1") (pintype "passive"))
      (node (ref "R16") (pin "2") (pinfunction "2_2") (pintype "passive"))
      (node (ref "R18") (pin "1") (pinfunction "1_1") (pintype "passive"))
      (node (ref "R19") (pin "2") (pinfunction "2_2") (pintype "passive"))
      (node (ref "R20") (pin "2") (pinfunction "2_2") (pintype "passive"))
      (node (ref "R21") (pin "2") (pinfunction "2_2") (pintype "passive"))
      (node (ref "R3") (pin "2") (pinfunction "2_2") (pintype "passive"))
      (node (ref "R7") (pin "2") (pinfunction "2_2") (pintype "passive"))
      (node (ref "R8") (pin "1") (pinfunction "1_1") (pintype "passive"))
      (node (ref "R9") (pin "1") (pinfunction "1_1") (pintype "passive"))
      (node (ref "SDHC") (pin "4") (pinfunction "VDD_4") (pintype "passive"))
      (node (ref "SW2") (pin "1") (pinfunction "I/O1_1") (pintype "passive"))
      (node (ref "SW3") (pin "3") (pinfunction "I/O2_3") (pintype "passive"))
      (node (ref "SWD") (pin "4") (pinfunction "4_4") (pintype "passive"))
      (node (ref "U1") (pin "19") (pinfunction "VDD_4_19") (pintype "power_in"))
      (node (ref "U1") (pin "32") (pinfunction "VDD_1_32") (pintype "power_in"))
      (node (ref "U1") (pin "48") (pinfunction "VDD_2_48") (pintype "power_in"))
      (node (ref "U1") (pin "64") (pinfunction "VDD_3_64") (pintype "power_in"))
    )
    (net (code "58") (name "5V_IN") (class "Default")
      (node (ref "P2") (pin "2") (pinfunction "2_2") (pintype "passive"))
      (node (ref "SW1") (pin "4") (pinfunction "4_4") (pintype "passive"))
      (node (ref "SW1") (pin "5") (pinfunction "5_5") (pintype "passive"))
    )
    (net (code "59") (name "5V_USB") (class "Default")
      (node (ref "C19") (pin "2") (pinfunction "2_2") (pintype "passive"))
      (node (ref "C7") (pin "2") (pinfunction "2_2") (pintype "passive"))
      (node (ref "CON1") (pin "A4") (pinfunction "VBUS_A4") (pintype "passive"))
      (node (ref "CON1") (pin "A9") (pinfunction "VBUS_A9") (pintype "passive"))
      (node (ref "CON1") (pin "B4") (pinfunction "VBUS_B4") (pintype "passive"))
      (node (ref "CON1") (pin "B9") (pinfunction "VBUS_B9") (pintype "passive"))
      (node (ref "CON2") (pin "A4") (pinfunction "VBUS_A4") (pintype "passive"))
      (node (ref "CON2") (pin "A9") (pinfunction "VBUS_A9") (pintype "passive"))
      (node (ref "CON2") (pin "B4") (pinfunction "VBUS_B4") (pintype "passive"))
      (node (ref "CON2") (pin "B9") (pinfunction "VBUS_B9") (pintype "passive"))
      (node (ref "SW1") (pin "1") (pinfunction "1_1") (pintype "passive"))
      (node (ref "SW1") (pin "8") (pinfunction "8_8") (pintype "passive"))
      (node (ref "U2") (pin "7") (pinfunction "VREGIN_7") (pintype "passive"))
      (node (ref "U2") (pin "8") (pinfunction "VBUS_8") (pintype "passive"))
    )
    (net (code "60") (name "GND") (class "Default")
      (node (ref "3V3") (pin "1") (pinfunction "GND_1") (pintype "passive"))
      (node (ref "C1") (pin "1") (pinfunction "1_1") (pintype "passive"))
      (node (ref "C10") (pin "2") (pinfunction "2_2") (pintype "passive"))
      (node (ref "C11") (pin "2") (pinfunction "2_2") (pintype "passive"))
      (node (ref "C12") (pin "1") (pinfunction "1_1") (pintype "passive"))
      (node (ref "C13") (pin "1") (pinfunction "1_1") (pintype "passive"))
      (node (ref "C14") (pin "1") (pinfunction "1_1") (pintype "passive"))
      (node (ref "C15") (pin "1") (pinfunction "1_1") (pintype "passive"))
      (node (ref "C16") (pin "1") (pinfunction "1_1") (pintype "passive"))
      (node (ref "C17") (pin "1") (pinfunction "1_1") (pintype "passive"))
      (node (ref "C18") (pin "1") (pinfunction "1_1") (pintype "passive"))
      (node (ref "C19") (pin "1") (pinfunction "1_1") (pintype "passive"))
      (node (ref "C2") (pin "1") (pinfunction "1_1") (pintype "passive"))
      (node (ref "C20") (pin "1") (pinfunction "1_1") (pintype "passive"))
      (node (ref "C21") (pin "1") (pinfunction "1_1") (pintype "passive"))
      (node (ref "C22") (pin "1") (pinfunction "1_1") (pintype "passive"))
      (node (ref "C23") (pin "1") (pinfunction "1_1") (pintype "passive"))
      (node (ref "C24") (pin "1") (pinfunction "1_1") (pintype "passive"))
      (node (ref "C25") (pin "1") (pinfunction "1_1") (pintype "passive"))
      (node (ref "C3") (pin "1") (pinfunction "1_1") (pintype "passive"))
      (node (ref "C4") (pin "1") (pinfunction "1_1") (pintype "passive"))
      (node (ref "C5") (pin "1") (pinfunction "1_1") (pintype "passive"))
      (node (ref "C6") (pin "1") (pinfunction "1_1") (pintype "passive"))
      (node (ref "C7") (pin "1") (pinfunction "1_1") (pintype "passive"))
      (node (ref "C8") (pin "1") (pinfunction "1_1") (pintype "passive"))
      (node (ref "C9") (pin "1") (pinfunction "1_1") (pintype "passive"))
      (node (ref "CON1") (pin "A1") (pinfunction "GND_A1") (pintype "passive"))
      (node (ref "CON1") (pin "A12") (pinfunction "GND_A12") (pintype "passive"))
      (node (ref "CON1") (pin "B1") (pinfunction "GND_B1") (pintype "passive"))
      (node (ref "CON1") (pin "B12") (pinfunction "GND_B12") (pintype "passive"))
      (node (ref "CON1") (pin "D0") (pinfunction "Shield_D0") (pintype "passive"))
      (node (ref "CON2") (pin "A1") (pinfunction "GND_A1") (pintype "passive"))
      (node (ref "CON2") (pin "A12") (pinfunction "GND_A12") (pintype "passive"))
      (node (ref "CON2") (pin "B1") (pinfunction "GND_B1") (pintype "passive"))
      (node (ref "CON2") (pin "B12") (pinfunction "GND_B12") (pintype "passive"))
      (node (ref "CON2") (pin "D0") (pinfunction "Shield_D0") (pintype "passive"))
      (node (ref "D3") (pin "1") (pinfunction "A_1") (pintype "passive"))
      (node (ref "D4") (pin "1") (pinfunction "A_1") (pintype "passive"))
      (node (ref "D6") (pin "K") (pinfunction "K_K") (pintype "passive"))
      (node (ref "JTAG/SWD") (pin "10") (pinfunction "GND_10") (pintype "passive"))
      (node (ref "JTAG/SWD") (pin "12") (pinfunction "GND_12") (pintype "passive"))
      (node (ref "JTAG/SWD") (pin "14") (pinfunction "GND_14") (pintype "passive"))
      (node (ref "JTAG/SWD") (pin "16") (pinfunction "GND_16") (pintype "passive"))
      (node (ref "JTAG/SWD") (pin "18") (pinfunction "GND_18") (pintype "passive"))
      (node (ref "JTAG/SWD") (pin "20") (pinfunction "GND_20") (pintype "passive"))
      (node (ref "JTAG/SWD") (pin "4") (pinfunction "GND_4") (pintype "passive"))
      (node (ref "JTAG/SWD") (pin "6") (pinfunction "GND_6") (pintype "passive"))
      (node (ref "JTAG/SWD") (pin "8") (pinfunction "GND_8") (pintype "passive"))
      (node (ref "NOR") (pin "4") (pinfunction "GND_4") (pintype "passive"))
      (node (ref "NRF2401") (pin "1") (pinfunction "GND_1") (pintype "passive"))
      (node (ref "P1") (pin "1") (pinfunction "1_1") (pintype "passive"))
      (node (ref "P1") (pin "31") (pinfunction "31_31") (pintype "passive"))
      (node (ref "P2") (pin "1") (pinfunction "1_1") (pintype "passive"))
      (node (ref "P2") (pin "13") (pinfunction "13_13") (pintype "passive"))
      (node (ref "P2") (pin "31") (pinfunction "31_31") (pintype "passive"))
      (node (ref "R11") (pin "1") (pinfunction "1_1") (pintype "passive"))
      (node (ref "RESET") (pin "2") (pinfunction "2_2") (pintype "passive"))
      (node (ref "SDHC") (pin "11") (pinfunction "VSS2_11") (pintype "passive"))
      (node (ref "SDHC") (pin "12") (pinfunction "VSS3_12") (pintype "passive"))
      (node (ref "SDHC") (pin "13") (pinfunction "VSS4_13") (pintype "passive"))
      (node (ref "SDHC") (pin "14") (pinfunction "VSS5_14") (pintype "passive"))
      (node (ref "SDHC") (pin "6") (pinfunction "VSS1_6") (pintype "passive"))
      (node (ref "SW2") (pin "3") (pinfunction "I/O2_3") (pintype "passive"))
      (node (ref "SW3") (pin "1") (pinfunction "I/O1_1") (pintype "passive"))
      (node (ref "SWD") (pin "5") (pinfunction "5_5") (pintype "passive"))
      (node (ref "U1") (pin "12") (pinfunction "VSSA_12") (pintype "power_in"))
      (node (ref "U1") (pin "18") (pinfunction "VSS_4_18") (pintype "power_in"))
      (node (ref "U1") (pin "31") (pinfunction "VSS_1_31") (pintype "power_in"))
      (node (ref "U1") (pin "47") (pinfunction "VSS_2_47") (pintype "power_in"))
      (node (ref "U1") (pin "63") (pinfunction "VSS_3_63") (pintype "power_in"))
      (node (ref "U2") (pin "0") (pinfunction "GND_0") (pintype "passive"))
      (node (ref "U2") (pin "2") (pinfunction "GND_2") (pintype "passive"))
    )
    (net (code "61") (name "Net-(CON1-DN1(D-))") (class "Default")
      (node (ref "CON1") (pin "A7") (pinfunction "DN1(D-)_A7") (pintype "passive"))
      (node (ref "CON1") (pin "B7") (pinfunction "DN2(D-)_B7") (pintype "passive"))
      (node (ref "R5") (pin "1") (pinfunction "1_1") (pintype "passive"))
    )
    (net (code "62") (name "Net-(CON1-DP1(D+))") (class "Default")
      (node (ref "CON1") (pin "A6") (pinfunction "DP1(D+)_A6") (pintype "passive"))
      (node (ref "CON1") (pin "B6") (pinfunction "DP2(D+)_B6") (pintype "passive"))
      (node (ref "R6") (pin "1") (pinfunction "1_1") (pintype "passive"))
      (node (ref "R7") (pin "1") (pinfunction "1_1") (pintype "passive"))
    )
    (net (code "63") (name "Net-(CON2-DN1(D-))") (class "Default")
      (node (ref "CON2") (pin "A7") (pinfunction "DN1(D-)_A7") (pintype "passive"))
      (node (ref "CON2") (pin "B7") (pinfunction "DN2(D-)_B7") (pintype "passive"))
      (node (ref "R4") (pin "1") (pinfunction "1_1") (pintype "passive"))
    )
    (net (code "64") (name "Net-(CON2-DP1(D+))") (class "Default")
      (node (ref "CON2") (pin "A6") (pinfunction "DP1(D+)_A6") (pintype "passive"))
      (node (ref "CON2") (pin "B6") (pinfunction "DP2(D+)_B6") (pintype "passive"))
      (node (ref "R14") (pin "1") (pinfunction "1_1") (pintype "passive"))
      (node (ref "R16") (pin "1") (pinfunction "1_1") (pintype "passive"))
    )
    (net (code "65") (name "Net-(D1-K)") (class "Default")
      (node (ref "C1") (pin "2") (pinfunction "2_2") (pintype "passive"))
      (node (ref "D1") (pin "3") (pinfunction "K_3") (pintype "passive"))
      (node (ref "U1") (pin "1") (pinfunction "VBAT_1") (pintype "power_in"))
    )
    (net (code "66") (name "Net-(D2-PadA)") (class "Default")
      (node (ref "D2") (pin "A") (pinfunction "A_A") (pintype "passive"))
      (node (ref "R17") (pin "1") (pinfunction "1_1") (pintype "passive"))
    )
    (net (code "67") (name "Net-(D5-PadA)") (class "Default")
      (node (ref "D5") (pin "A") (pinfunction "A_A") (pintype "passive"))
      (node (ref "R22") (pin "1") (pinfunction "1_1") (pintype "passive"))
    )
    (net (code "68") (name "Net-(D6-PadA)") (class "Default")
      (node (ref "D6") (pin "A") (pinfunction "A_A") (pintype "passive"))
      (node (ref "R21") (pin "1") (pinfunction "1_1") (pintype "passive"))
    )
    (net (code "69") (name "Net-(D7-PadA)") (class "Default")
      (node (ref "D7") (pin "A") (pinfunction "A_A") (pintype "passive"))
      (node (ref "R20") (pin "1") (pinfunction "1_1") (pintype "passive"))
    )
    (net (code "70") (name "Net-(D8-PadA)") (class "Default")
      (node (ref "D8") (pin "A") (pinfunction "A_A") (pintype "passive"))
      (node (ref "R19") (pin "1") (pinfunction "1_1") (pintype "passive"))
    )
    (net (code "71") (name "Net-(NRF2401-IRQ)") (class "Default")
      (node (ref "NRF2401") (pin "8") (pinfunction "IRQ_8") (pintype "passive"))
      (node (ref "R13") (pin "1") (pinfunction "1_1") (pintype "passive"))
    )
    (net (code "72") (name "Net-(SW2-COM1)") (class "Default")
      (node (ref "R1") (pin "2") (pinfunction "2_2") (pintype "passive"))
      (node (ref "SW2") (pin "2") (pinfunction "COM1_2") (pintype "passive"))
    )
    (net (code "73") (name "Net-(SW3-COM1)") (class "Default")
      (node (ref "R2") (pin "1") (pinfunction "1_1") (pintype "passive"))
      (node (ref "SW3") (pin "2") (pinfunction "COM1_2") (pintype "passive"))
    )
    (net (code "74") (name "Net-(U1B-VDDA)") (class "Default")
      (node (ref "C8") (pin "2") (pinfunction "2_2") (pintype "passive"))
      (node (ref "C9") (pin "2") (pinfunction "2_2") (pintype "passive"))
      (node (ref "R18") (pin "2") (pinfunction "2_2") (pintype "passive"))
      (node (ref "U1") (pin "13") (pinfunction "VDDA_13") (pintype "power_in"))
    )
    (net (code "75") (name "Net-(U2-RXD)") (class "Default")
      (node (ref "R25") (pin "1") (pinfunction "1_1") (pintype "passive"))
      (node (ref "U2") (pin "20") (pinfunction "RXD_20") (pintype "passive"))
    )
    (net (code "76") (name "Net-(U2-RXT{slash}GPIO1)") (class "Default")
      (node (ref "D5") (pin "K") (pinfunction "K_K") (pintype "passive"))
      (node (ref "U2") (pin "13") (pinfunction "RXT/GPIO1_13") (pintype "passive"))
    )
    (net (code "77") (name "Net-(U2-TXD)") (class "Default")
      (node (ref "R24") (pin "1") (pinfunction "1_1") (pintype "passive"))
      (node (ref "U2") (pin "21") (pinfunction "TXD_21") (pintype "passive"))
    )
    (net (code "78") (name "Net-(U2-TXT{slash}GPIO0)") (class "Default")
      (node (ref "D2") (pin "K") (pinfunction "K_K") (pintype "passive"))
      (node (ref "U2") (pin "14") (pinfunction "TXT/GPIO0_14") (pintype "passive"))
    )
    (net (code "79") (name "Net-(U2-~{RST})") (class "Default")
      (node (ref "R23") (pin "2") (pinfunction "2_2") (pintype "passive"))
      (node (ref "U2") (pin "9") (pinfunction "~{RST}_9") (pintype "passive"))
    )
    (net (code "80") (name "VBAT") (class "Default")
      (node (ref "D1") (pin "2") (pinfunction "A_2") (pintype "passive"))
      (node (ref "P2") (pin "30") (pinfunction "30_30") (pintype "passive"))
    )
    (net (code "81") (name "VIO") (class "Default")
      (node (ref "C23") (pin "2") (pinfunction "2_2") (pintype "passive"))
      (node (ref "C25") (pin "2") (pinfunction "2_2") (pintype "passive"))
      (node (ref "R17") (pin "2") (pinfunction "2_2") (pintype "passive"))
      (node (ref "R22") (pin "2") (pinfunction "2_2") (pintype "passive"))
      (node (ref "R23") (pin "1") (pinfunction "1_1") (pintype "passive"))
      (node (ref "U2") (pin "5") (pinfunction "VIO_5") (pintype "passive"))
      (node (ref "U2") (pin "6") (pinfunction "VDD_6") (pintype "passive"))
    )
    (net (code "82") (name "unconnected-(3V3-Vout-Pad4)") (class "Default")
      (node (ref "3V3") (pin "4") (pinfunction "Vout_4") (pintype "passive"))
    )
    (net (code "83") (name "unconnected-(CON1-CC1-PadA5)") (class "Default")
      (node (ref "CON1") (pin "A5") (pinfunction "CC1_A5") (pintype "passive"))
    )
    (net (code "84") (name "unconnected-(CON1-CC2-PadB5)") (class "Default")
      (node (ref "CON1") (pin "B5") (pinfunction "CC2_B5") (pintype "passive"))
    )
    (net (code "85") (name "unconnected-(CON1-SBU1-PadA8)") (class "Default")
      (node (ref "CON1") (pin "A8") (pinfunction "SBU1_A8") (pintype "passive"))
    )
    (net (code "86") (name "unconnected-(CON1-SBU2-PadB8)") (class "Default")
      (node (ref "CON1") (pin "B8") (pinfunction "SBU2_B8") (pintype "passive"))
    )
    (net (code "87") (name "unconnected-(CON2-CC1-PadA5)") (class "Default")
      (node (ref "CON2") (pin "A5") (pinfunction "CC1_A5") (pintype "passive"))
    )
    (net (code "88") (name "unconnected-(CON2-CC2-PadB5)") (class "Default")
      (node (ref "CON2") (pin "B5") (pinfunction "CC2_B5") (pintype "passive"))
    )
    (net (code "89") (name "unconnected-(CON2-SBU1-PadA8)") (class "Default")
      (node (ref "CON2") (pin "A8") (pinfunction "SBU1_A8") (pintype "passive"))
    )
    (net (code "90") (name "unconnected-(CON2-SBU2-PadB8)") (class "Default")
      (node (ref "CON2") (pin "B8") (pinfunction "SBU2_B8") (pintype "passive"))
    )
    (net (code "91") (name "unconnected-(JTAG/SWD-NC-Pad11)") (class "Default")
      (node (ref "JTAG/SWD") (pin "11") (pinfunction "NC_11") (pintype "passive+no_connect"))
    )
    (net (code "92") (name "unconnected-(JTAG/SWD-NC-Pad17)") (class "Default")
      (node (ref "JTAG/SWD") (pin "17") (pinfunction "NC_17") (pintype "passive+no_connect"))
    )
    (net (code "93") (name "unconnected-(JTAG/SWD-NC-Pad19)") (class "Default")
      (node (ref "JTAG/SWD") (pin "19") (pinfunction "NC_19") (pintype "passive+no_connect"))
    )
    (net (code "94") (name "unconnected-(SDHC-CD_COMMON-Pad10)") (class "Default")
      (node (ref "SDHC") (pin "10") (pinfunction "CD_COMMON_10") (pintype "passive"))
    )
    (net (code "95") (name "unconnected-(SDHC-CD_SW-Pad9)") (class "Default")
      (node (ref "SDHC") (pin "9") (pinfunction "CD_SW_9") (pintype "passive"))
    )
    (net (code "96") (name "unconnected-(SDHC-DAT1-Pad8)") (class "Default")
      (node (ref "SDHC") (pin "8") (pinfunction "DAT1_8") (pintype "passive"))
    )
    (net (code "97") (name "unconnected-(SDHC-DAT2-Pad1)") (class "Default")
      (node (ref "SDHC") (pin "1") (pinfunction "DAT2_1") (pintype "passive"))
    )
    (net (code "98") (name "unconnected-(U2-CTS-Pad18)") (class "Default")
      (node (ref "U2") (pin "18") (pinfunction "CTS_18") (pintype "passive"))
    )
    (net (code "99") (name "unconnected-(U2-DCD-Pad24)") (class "Default")
      (node (ref "U2") (pin "24") (pinfunction "DCD_24") (pintype "passive"))
    )
    (net (code "100") (name "unconnected-(U2-DSR-Pad22)") (class "Default")
      (node (ref "U2") (pin "22") (pinfunction "DSR_22") (pintype "passive"))
    )
    (net (code "101") (name "unconnected-(U2-DTR-Pad23)") (class "Default")
      (node (ref "U2") (pin "23") (pinfunction "DTR_23") (pintype "passive"))
    )
    (net (code "102") (name "unconnected-(U2-NC-Pad10)") (class "Default")
      (node (ref "U2") (pin "10") (pinfunction "NC_10") (pintype "passive+no_connect"))
    )
    (net (code "103") (name "unconnected-(U2-NC-Pad16)") (class "Default")
      (node (ref "U2") (pin "16") (pinfunction "NC_16") (pintype "passive+no_connect"))
    )
    (net (code "104") (name "unconnected-(U2-RI{slash}CLK-Pad1)") (class "Default")
      (node (ref "U2") (pin "1") (pinfunction "RI/CLK_1") (pintype "passive"))
    )
    (net (code "105") (name "unconnected-(U2-RS485{slash}GPIO2-Pad12)") (class "Default")
      (node (ref "U2") (pin "12") (pinfunction "RS485/GPIO2_12") (pintype "passive"))
    )
    (net (code "106") (name "unconnected-(U2-RTS-Pad19)") (class "Default")
      (node (ref "U2") (pin "19") (pinfunction "RTS_19") (pintype "passive"))
    )
    (net (code "107") (name "unconnected-(U2-SUSPEND-Pad17)") (class "Default")
      (node (ref "U2") (pin "17") (pinfunction "SUSPEND_17") (pintype "passive"))
    )
    (net (code "108") (name "unconnected-(U2-WAKUP{slash}GPIO3-Pad11)") (class "Default")
      (node (ref "U2") (pin "11") (pinfunction "WAKUP/GPIO3_11") (pintype "passive"))
    )
    (net (code "109") (name "unconnected-(U2-~{SUSPEND}-Pad15)") (class "Default")
      (node (ref "U2") (pin "15") (pinfunction "~{SUSPEND}_15") (pintype "passive"))
    )
  )
)
